# M8_PCB.net
KiCad netlist of a schematic drawn in EAGLE
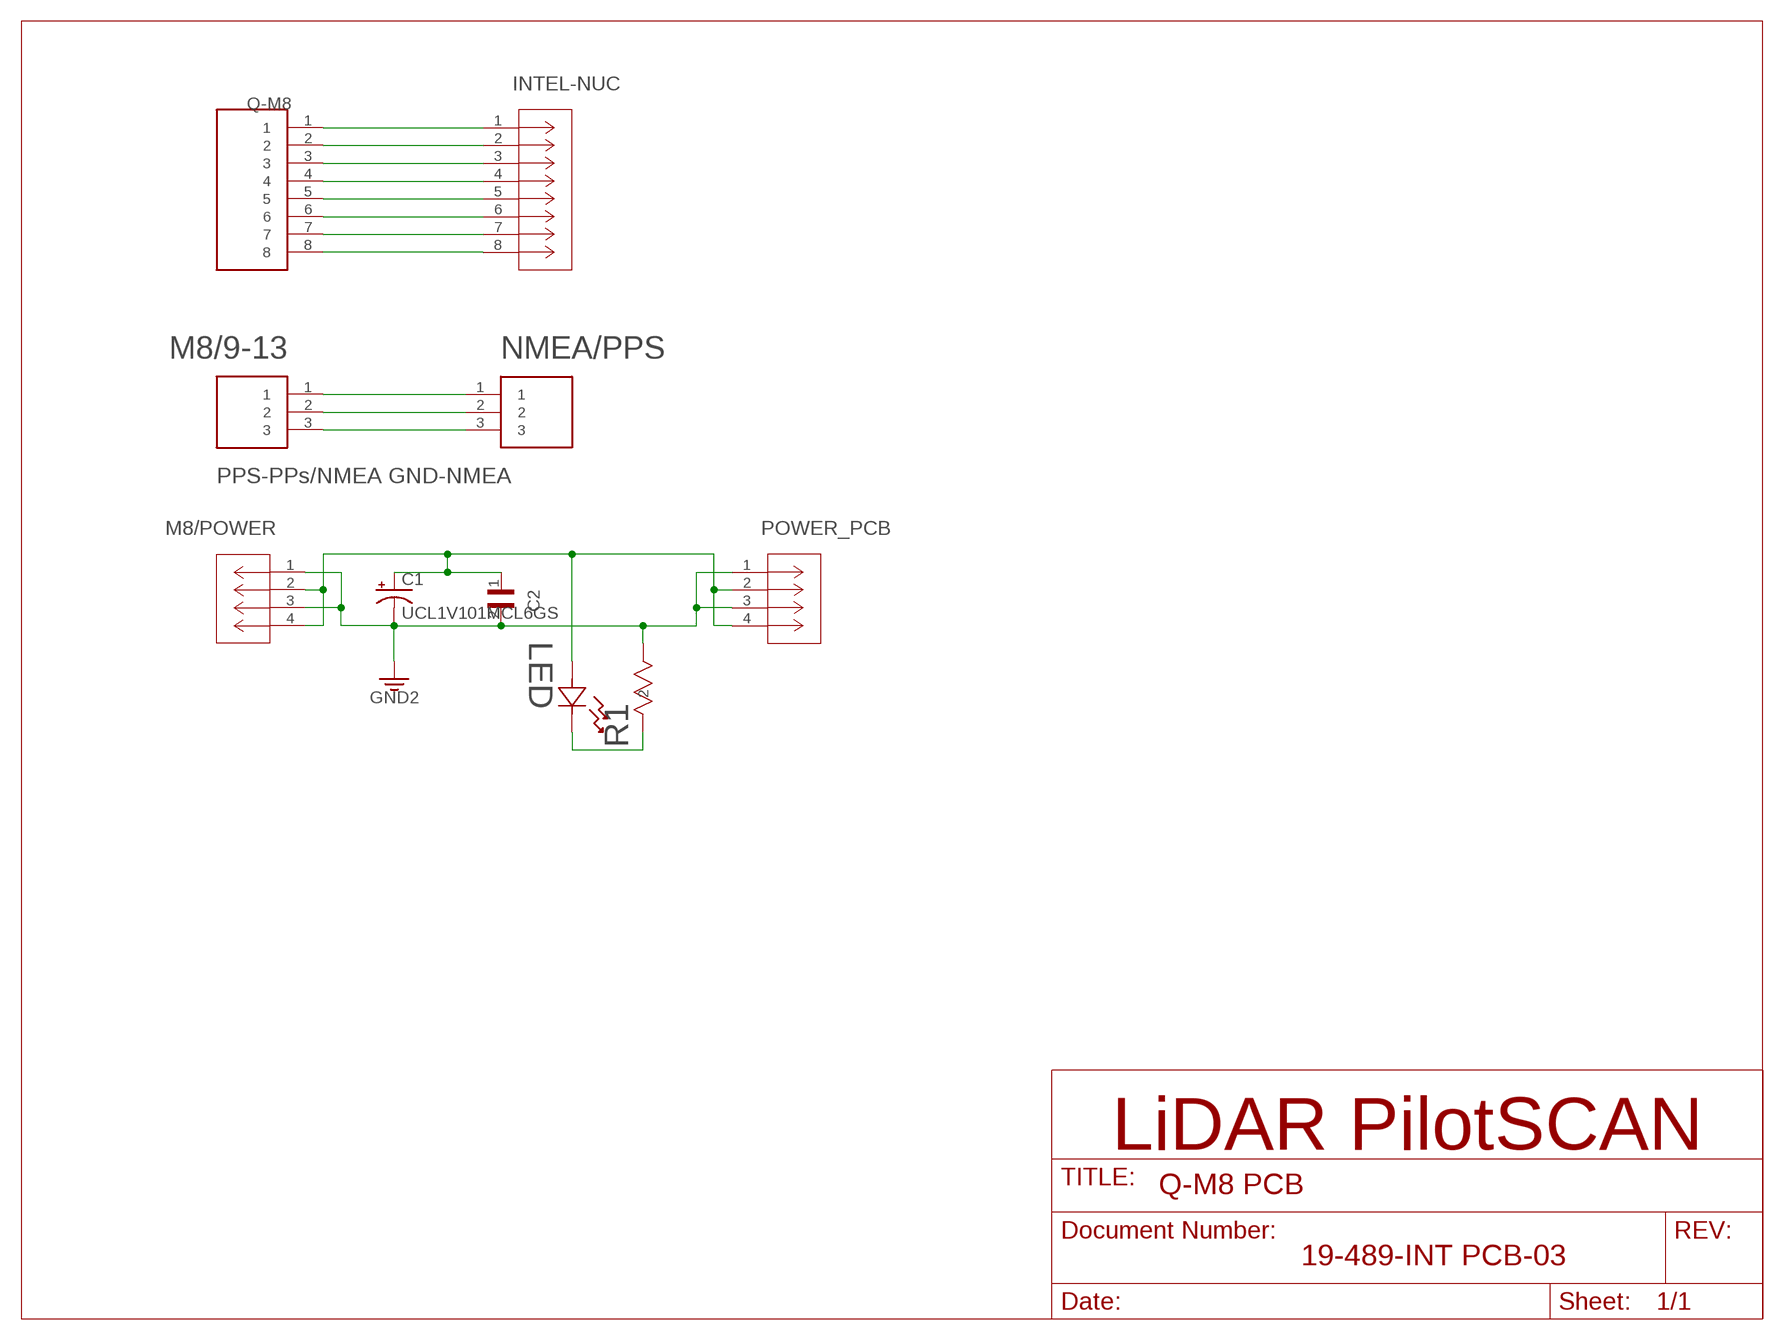
[diagram p0: schematic, sheet 1]

(export (version "E")
  (design (tool "Eeschema 10.0.6"))
  (components
    (comp (ref "C1")
      (value "UCL1V101MCL6GS")
      (footprint "eagle-import:U2-K")
      (libsource (lib "eagle-import") (part "UCL1V101MCL6GS"))
    )
    (comp (ref "C2")
      (value "GRM033R6YA104KE14D")
      (footprint "eagle-import:CAPC0603X33N")
      (fields (field (name "DIGI-KEY_PART_NUMBER") "490-10430-1-ND") (field (name "MF") "Murata Electronics"))
      (libsource (lib "eagle-import") (part "GRM033R6YA104KE14D"))
    )
    (comp (ref "INTEL-NUC")
      (value "LLC")
      (footprint "eagle-import:0955032881")
      (libsource (lib "eagle-import") (part "LLC"))
    )
    (comp (ref "LED")
      (value "VLMC3100-GS08")
      (footprint "eagle-import:LED_PLCC_VSMB")
      (fields (field (name "MANUFACTURER_PART_NUMBER") "VLMC3100GS08"))
      (libsource (lib "eagle-import") (part "VLMC3100-GS08"))
    )
    (comp (ref "M8/9-13")
      (value "1-2834021-3")
      (footprint "eagle-import:CONN_1-2834021-3")
      (fields (field (name "DIGI-KEY_PART_NUMBER") "A123845-ND") (field (name "MF") "TE Connectivity"))
      (libsource (lib "eagle-import") (part "1-2834021-3"))
    )
    (comp (ref "M8/POWER")
      (value "3-794630-4")
      (footprint "eagle-import:CON4_2X2_P3MM_VMNL2")
      (fields (field (name "MANUFACTURER_PART_NUMBER") "37946304"))
      (libsource (lib "eagle-import") (part "3-794630-4"))
    )
    (comp (ref "NMEA/PPS")
      (value "1-2834021-3")
      (footprint "eagle-import:CONN_1-2834021-3")
      (fields (field (name "DIGI-KEY_PART_NUMBER") "A123845-ND") (field (name "MF") "TE Connectivity"))
      (libsource (lib "eagle-import") (part "1-2834021-3"))
    )
    (comp (ref "POWER_PCB")
      (value "3-794630-4")
      (footprint "eagle-import:CON4_2X2_P3MM_VMNL2")
      (fields (field (name "MANUFACTURER_PART_NUMBER") "37946304"))
      (libsource (lib "eagle-import") (part "3-794630-4"))
    )
    (comp (ref "Q-M8")
      (value "292133-8")
      (footprint "eagle-import:TE_292133-8")
      (fields (field (name "DIGI-KEY_PART_NUMBER") "A100950-ND") (field (name "MF") "TE Connectivity"))
      (libsource (lib "eagle-import") (part "292133-8"))
    )
    (comp (ref "R1")
      (value "CRCW04026K80FKEDHP")
      (footprint "eagle-import:RES_CRCW_0402")
      (libsource (lib "eagle-import") (part "CRCW04026K80FKEDHP"))
    )
  )
  (nets
    (net (code "1") (name "GND2") (class "Default")
      (node (ref "C1") (pin "2") (pinfunction "-_2") (pintype "passive"))
      (node (ref "C2") (pin "2") (pinfunction "2_2") (pintype "passive"))
      (node (ref "M8/POWER") (pin "1") (pinfunction "1_1") (pintype "passive"))
      (node (ref "M8/POWER") (pin "3") (pinfunction "3_3") (pintype "passive"))
      (node (ref "POWER_PCB") (pin "1") (pinfunction "1_1") (pintype "passive"))
      (node (ref "POWER_PCB") (pin "3") (pinfunction "3_3") (pintype "passive"))
      (node (ref "R1") (pin "1") (pinfunction "1_1") (pintype "passive"))
    )
    (net (code "2") (name "Net-(C1-+)") (class "Default")
      (node (ref "C1") (pin "1") (pinfunction "+_1") (pintype "passive"))
      (node (ref "C2") (pin "1") (pinfunction "1_1") (pintype "passive"))
      (node (ref "LED") (pin "2") (pinfunction "2_2") (pintype "passive"))
      (node (ref "M8/POWER") (pin "2") (pinfunction "2_2") (pintype "passive"))
      (node (ref "M8/POWER") (pin "4") (pinfunction "4_4") (pintype "passive"))
      (node (ref "POWER_PCB") (pin "2") (pinfunction "2_2") (pintype "passive"))
      (node (ref "POWER_PCB") (pin "4") (pinfunction "4_4") (pintype "passive"))
    )
    (net (code "3") (name "Net-(INTEL-NUC-Pad1)") (class "Default")
      (node (ref "INTEL-NUC") (pin "1") (pinfunction "1_1") (pintype "passive"))
      (node (ref "Q-M8") (pin "1") (pinfunction "1_1") (pintype "passive"))
    )
    (net (code "4") (name "Net-(INTEL-NUC-Pad2)") (class "Default")
      (node (ref "INTEL-NUC") (pin "2") (pinfunction "2_2") (pintype "passive"))
      (node (ref "Q-M8") (pin "2") (pinfunction "2_2") (pintype "passive"))
    )
    (net (code "5") (name "Net-(INTEL-NUC-Pad3)") (class "Default")
      (node (ref "INTEL-NUC") (pin "3") (pinfunction "3_3") (pintype "passive"))
      (node (ref "Q-M8") (pin "3") (pinfunction "3_3") (pintype "passive"))
    )
    (net (code "6") (name "Net-(INTEL-NUC-Pad4)") (class "Default")
      (node (ref "INTEL-NUC") (pin "4") (pinfunction "4_4") (pintype "passive"))
      (node (ref "Q-M8") (pin "4") (pinfunction "4_4") (pintype "passive"))
    )
    (net (code "7") (name "Net-(INTEL-NUC-Pad5)") (class "Default")
      (node (ref "INTEL-NUC") (pin "5") (pinfunction "5_5") (pintype "passive"))
      (node (ref "Q-M8") (pin "5") (pinfunction "5_5") (pintype "passive"))
    )
    (net (code "8") (name "Net-(INTEL-NUC-Pad6)") (class "Default")
      (node (ref "INTEL-NUC") (pin "6") (pinfunction "6_6") (pintype "passive"))
      (node (ref "Q-M8") (pin "6") (pinfunction "6_6") (pintype "passive"))
    )
    (net (code "9") (name "Net-(INTEL-NUC-Pad7)") (class "Default")
      (node (ref "INTEL-NUC") (pin "7") (pinfunction "7_7") (pintype "passive"))
      (node (ref "Q-M8") (pin "7") (pinfunction "7_7") (pintype "passive"))
    )
    (net (code "10") (name "Net-(INTEL-NUC-Pad8)") (class "Default")
      (node (ref "INTEL-NUC") (pin "8") (pinfunction "8_8") (pintype "passive"))
      (node (ref "Q-M8") (pin "8") (pinfunction "8_8") (pintype "passive"))
    )
    (net (code "11") (name "Net-(LED-Pad1)") (class "Default")
      (node (ref "LED") (pin "1") (pinfunction "1_1") (pintype "passive"))
      (node (ref "R1") (pin "2") (pinfunction "2_2") (pintype "passive"))
    )
    (net (code "12") (name "Net-(M8/9-13-Pad1)") (class "Default")
      (node (ref "M8/9-13") (pin "1") (pinfunction "1_1") (pintype "passive"))
      (node (ref "NMEA/PPS") (pin "1") (pinfunction "1_1") (pintype "passive"))
    )
    (net (code "13") (name "Net-(M8/9-13-Pad2)") (class "Default")
      (node (ref "M8/9-13") (pin "2") (pinfunction "2_2") (pintype "passive"))
      (node (ref "NMEA/PPS") (pin "2") (pinfunction "2_2") (pintype "passive"))
    )
    (net (code "14") (name "Net-(M8/9-13-Pad3)") (class "Default")
      (node (ref "M8/9-13") (pin "3") (pinfunction "3_3") (pintype "passive"))
      (node (ref "NMEA/PPS") (pin "3") (pinfunction "3_3") (pintype "passive"))
    )
  )
)
